# tof_board.net
KiCad netlist of a schematic drawn in Altium Designer
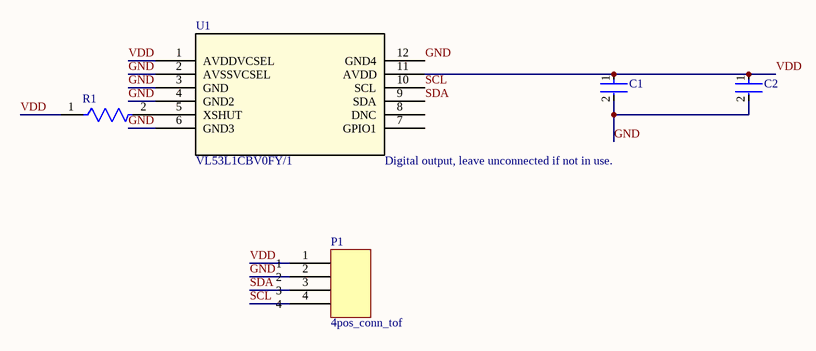
[diagram p0: tof_board.SchDoc]

(export (version "E")
  (design (tool "Eeschema 10.0.6"))
  (components
    (comp (ref "C1")
      (value "C0402C104K8PACTU")
      (footprint "FP-C0402-BB-MFG")
      (description "CAP CER 0.1UF 10V X5R 0402")
      (fields (field (name "MANUFACTURER") "Kemet") (field (name "TOLERANCE") "0.1"))
      (libsource (lib "Altium Content Vault") (part "b4654b650e69147ec39a6b967a45e02"))
    )
    (comp (ref "C2")
      (value "GRM155R60J475ME47D")
      (footprint "FP-GRM155-0_1-IPC_B")
      (description "Chip Multilayer Ceramic Capacitors for General Purpose, 0402, 4.7uF, X5R, 15%, 20%, 6.3V")
      (fields (field (name "VOLTAGE") "6.3V") (field (name "TOLERANCE") "20%"))
      (libsource (lib "Altium Content Vault") (part "11868f565c42a9108669ba33697ecf6"))
    )
    (comp (ref "P1")
      (value "4pos_conn_tof")
      (footprint "4pos_conn_tof")
      (libsource (lib "tof_board") (part "4pos_conn_tof"))
    )
    (comp (ref "R1")
      (value "ERA-3AEB103V")
      (footprint "FP-ERA3A-IPC_C")
      (description "RES SMD 10K OHM 0.1% 1/10W 0603")
      (fields (field (name "TOLERANCE") "0.1%"))
      (libsource (lib "Altium Content Vault") (part "4e5f8b3dd332802e91518312df5df73"))
    )
    (comp (ref "U1")
      (value "VL53L1CBV0FY/1")
      (footprint "QFN_BV0FY/1_STM")
      (description "No Description Available")
      (fields (field (name "COPYRIGHT") "Copyright (C) 2022 Ultra Librarian. All rights reserved."))
      (libsource (lib "tof_board") (part "VL53L1CBV0FY/1"))
    )
  )
  (nets
    (net (code "1") (name "/GND") (class "Default")
      (node (ref "C1") (pin "2") (pinfunction "2_2") (pintype "passive"))
      (node (ref "C2") (pin "2") (pinfunction "2_2") (pintype "passive"))
      (node (ref "U1") (pin "12") (pinfunction "GND4_12") (pintype "passive"))
      (node (ref "U1") (pin "2") (pinfunction "AVSSVCSEL_2") (pintype "passive"))
      (node (ref "U1") (pin "3") (pinfunction "GND_3") (pintype "passive"))
      (node (ref "U1") (pin "4") (pinfunction "GND2_4") (pintype "passive"))
      (node (ref "U1") (pin "6") (pinfunction "GND3_6") (pintype "passive"))
    )
    (net (code "2") (name "/SCL") (class "Default")
      (node (ref "U1") (pin "10") (pinfunction "SCL_10") (pintype "passive"))
    )
    (net (code "3") (name "/SDA") (class "Default")
      (node (ref "U1") (pin "9") (pinfunction "SDA_9") (pintype "passive"))
    )
    (net (code "4") (name "/VDD") (class "Default")
      (node (ref "C1") (pin "1") (pinfunction "1_1") (pintype "passive"))
      (node (ref "C2") (pin "1") (pinfunction "1_1") (pintype "passive"))
      (node (ref "R1") (pin "1") (pinfunction "1_1") (pintype "passive"))
      (node (ref "U1") (pin "1") (pinfunction "AVDDVCSEL_1") (pintype "power_in"))
      (node (ref "U1") (pin "11") (pinfunction "AVDD_11") (pintype "power_in"))
    )
    (net (code "5") (name "Net-(U1-XSHUT)") (class "Default")
      (node (ref "R1") (pin "2") (pinfunction "2_2") (pintype "passive"))
      (node (ref "U1") (pin "5") (pinfunction "XSHUT_5") (pintype "passive"))
    )
    (net (code "6") (name "unconnected-(P1-Pad1)") (class "Default")
      (node (ref "P1") (pin "1") (pinfunction "1_1") (pintype "passive"))
    )
    (net (code "7") (name "unconnected-(P1-Pad2)") (class "Default")
      (node (ref "P1") (pin "2") (pinfunction "2_2") (pintype "passive"))
    )
    (net (code "8") (name "unconnected-(P1-Pad3)") (class "Default")
      (node (ref "P1") (pin "3") (pinfunction "3_3") (pintype "passive"))
    )
    (net (code "9") (name "unconnected-(P1-Pad4)") (class "Default")
      (node (ref "P1") (pin "4") (pinfunction "4_4") (pintype "passive"))
    )
    (net (code "10") (name "unconnected-(U1-DNC-Pad8)") (class "Default")
      (node (ref "U1") (pin "8") (pinfunction "DNC_8") (pintype "passive"))
    )
    (net (code "11") (name "unconnected-(U1-GPIO1-Pad7)") (class "Default")
      (node (ref "U1") (pin "7") (pinfunction "GPIO1_7") (pintype "passive"))
    )
  )
)
